# LPC_11C14.net
KiCad netlist of a schematic drawn in Altium Designer
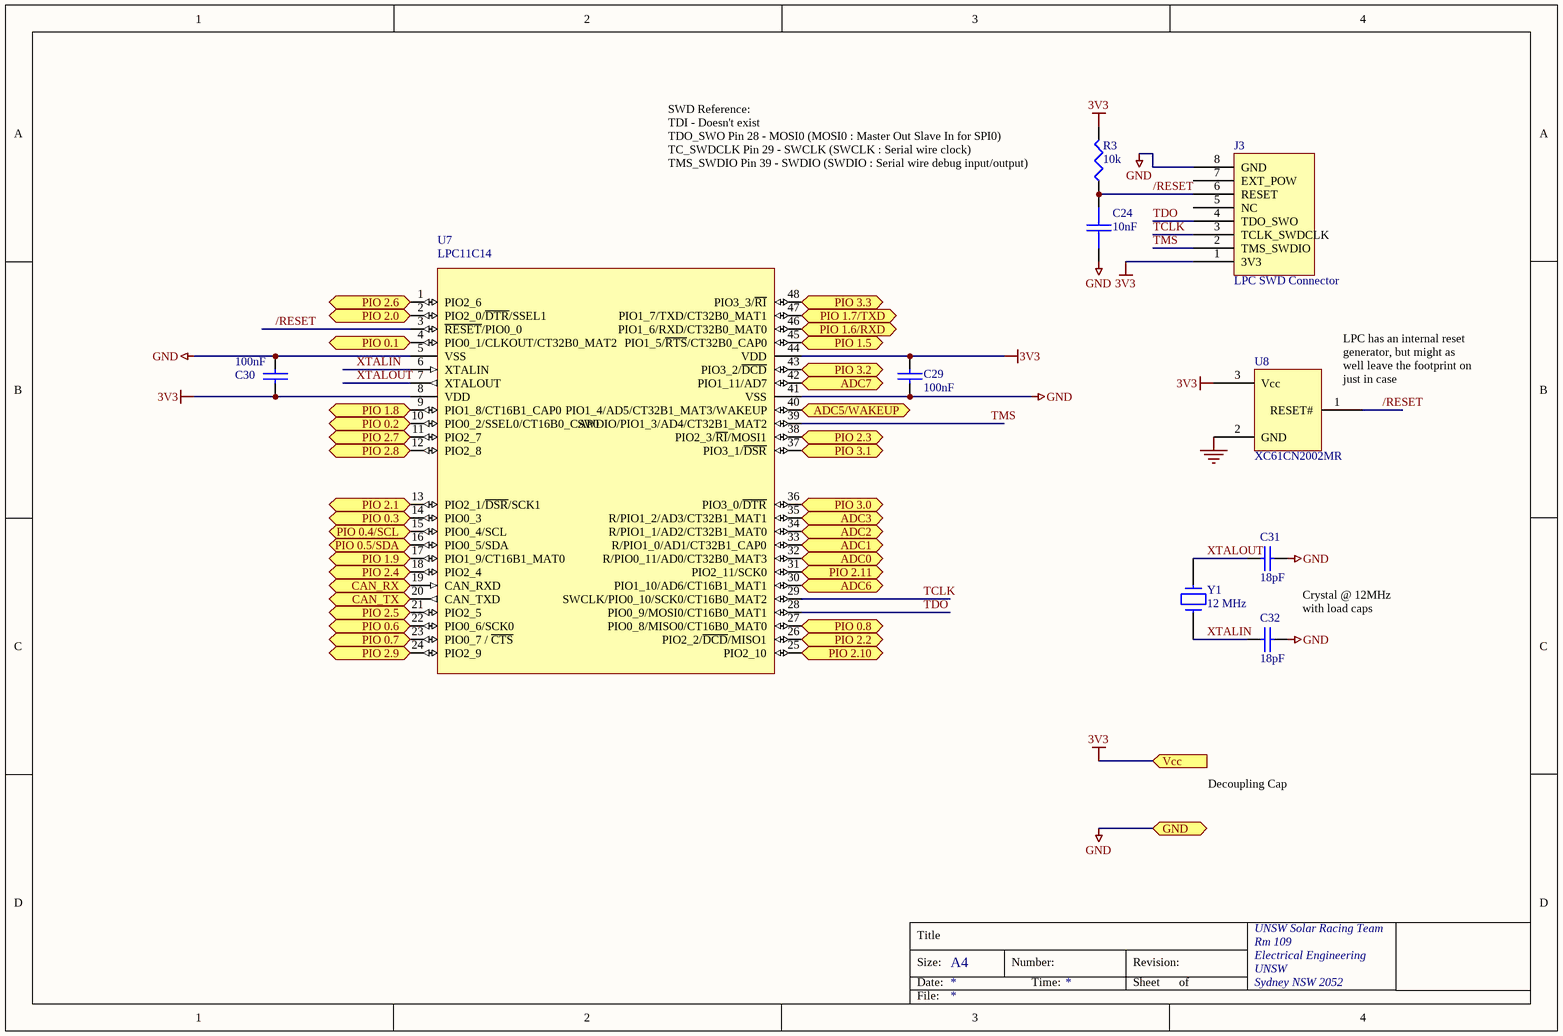
[diagram p0: LPC_11C14.SchDoc]

(export (version "E")
  (design (tool "Eeschema 10.0.6"))
  (components
    (comp (ref "C24")
      (value "10nF")
      (footprint "0603")
      (description "Capacitor")
      (libsource (lib "SunswiftLib20030312RR") (part "CAP"))
    )
    (comp (ref "C29")
      (value "100nF")
      (footprint "0603")
      (description "Capacitor")
      (libsource (lib "*") (part "CAP"))
    )
    (comp (ref "C30")
      (value "100nF")
      (footprint "0603")
      (description "Capacitor")
      (libsource (lib "*") (part "CAP"))
    )
    (comp (ref "C31")
      (value "18pF")
      (footprint "0603")
      (description "Capacitor")
      (libsource (lib "*") (part "CAP"))
    )
    (comp (ref "C32")
      (value "18pF")
      (footprint "0603")
      (description "Capacitor")
      (libsource (lib "*") (part "CAP"))
    )
    (comp (ref "J3")
      (value "LPC SWD Connector")
      (footprint "IDC8")
      (libsource (lib "2009_BatteryMaster") (part "LPCLink_Connector"))
    )
    (comp (ref "R3")
      (value "10k")
      (footprint "0603")
      (description "Resistor")
      (libsource (lib "SunswiftLib20030312RR") (part "RES1"))
    )
    (comp (ref "U7")
      (value "LPC11C14")
      (footprint "QFP48-long")
      (libsource (lib "LPC") (part "LPC11C14_Full"))
    )
    (comp (ref "U8")
      (value "XC61CN2002MR")
      (footprint "SOT23-3")
      (description "SOT23 reset generator")
      (libsource (lib "*") (part "XC61F"))
    )
    (comp (ref "Y1")
      (value "12 MHz")
      (footprint "HC49/4H")
      (description "Crystal")
      (libsource (lib "*") (part "CRYSTAL"))
    )
  )
  (nets
    (net (code "1") (name "/ADC0") (class "Default")
      (node (ref "U7") (pin "32") (pinfunction "R/PIO0_11/AD0/CT32B0_MAT3_32") (pintype "bidirectional"))
    )
    (net (code "2") (name "/ADC1") (class "Default")
      (node (ref "U7") (pin "33") (pinfunction "R/PIO1_0/AD1/CT32B1_CAP0_33") (pintype "bidirectional"))
    )
    (net (code "3") (name "/ADC2") (class "Default")
      (node (ref "U7") (pin "34") (pinfunction "R/PIO1_1/AD2/CT32B1_MAT0_34") (pintype "bidirectional"))
    )
    (net (code "4") (name "/ADC3") (class "Default")
      (node (ref "U7") (pin "35") (pinfunction "R/PIO1_2/AD3/CT32B1_MAT1_35") (pintype "bidirectional"))
    )
    (net (code "5") (name "/ADC5{slash}WAKEUP") (class "Default")
      (node (ref "U7") (pin "40") (pinfunction "PIO1_4/AD5/CT32B1_MAT3/WAKEUP_40") (pintype "bidirectional"))
    )
    (net (code "6") (name "/ADC6") (class "Default")
      (node (ref "U7") (pin "30") (pinfunction "PIO1_10/AD6/CT16B1_MAT1_30") (pintype "bidirectional"))
    )
    (net (code "7") (name "/ADC7") (class "Default")
      (node (ref "U7") (pin "42") (pinfunction "PIO1_11/AD7_42") (pintype "bidirectional"))
    )
    (net (code "8") (name "/CAN_RX") (class "Default")
      (node (ref "U7") (pin "19") (pinfunction "CAN_RXD_19") (pintype "input"))
    )
    (net (code "9") (name "/CAN_TX") (class "Default")
      (node (ref "U7") (pin "20") (pinfunction "CAN_TXD_20") (pintype "output"))
    )
    (net (code "10") (name "/PIO 0.1") (class "Default")
      (node (ref "U7") (pin "4") (pinfunction "PIO0_1/CLKOUT/CT32B0_MAT2_4") (pintype "bidirectional"))
    )
    (net (code "11") (name "/PIO 0.2") (class "Default")
      (node (ref "U7") (pin "10") (pinfunction "PIO0_2/SSEL0/CT16B0_CAP0_10") (pintype "bidirectional"))
    )
    (net (code "12") (name "/PIO 0.3") (class "Default")
      (node (ref "U7") (pin "14") (pinfunction "PIO0_3_14") (pintype "bidirectional"))
    )
    (net (code "13") (name "/PIO 0.4{slash}SCL") (class "Default")
      (node (ref "U7") (pin "15") (pinfunction "PIO0_4/SCL_15") (pintype "bidirectional"))
    )
    (net (code "14") (name "/PIO 0.5{slash}SDA") (class "Default")
      (node (ref "U7") (pin "16") (pinfunction "PIO0_5/SDA_16") (pintype "bidirectional"))
    )
    (net (code "15") (name "/PIO 0.6") (class "Default")
      (node (ref "U7") (pin "22") (pinfunction "PIO0_6/SCK0_22") (pintype "bidirectional"))
    )
    (net (code "16") (name "/PIO 0.7") (class "Default")
      (node (ref "U7") (pin "23") (pinfunction "PIO0_7_/_~{CTS}_23") (pintype "bidirectional"))
    )
    (net (code "17") (name "/PIO 0.8") (class "Default")
      (node (ref "U7") (pin "27") (pinfunction "PIO0_8/MISO0/CT16B0_MAT0_27") (pintype "bidirectional"))
    )
    (net (code "18") (name "/PIO 1.5") (class "Default")
      (node (ref "U7") (pin "45") (pinfunction "PIO1_5/~{RTS}/CT32B0_CAP0_45") (pintype "bidirectional"))
    )
    (net (code "19") (name "/PIO 1.6{slash}RXD") (class "Default")
      (node (ref "U7") (pin "46") (pinfunction "PIO1_6/RXD/CT32B0_MAT0_46") (pintype "bidirectional"))
    )
    (net (code "20") (name "/PIO 1.7{slash}TXD") (class "Default")
      (node (ref "U7") (pin "47") (pinfunction "PIO1_7/TXD/CT32B0_MAT1_47") (pintype "bidirectional"))
    )
    (net (code "21") (name "/PIO 1.8") (class "Default")
      (node (ref "U7") (pin "9") (pinfunction "PIO1_8/CT16B1_CAP0_9") (pintype "bidirectional"))
    )
    (net (code "22") (name "/PIO 1.9") (class "Default")
      (node (ref "U7") (pin "17") (pinfunction "PIO1_9/CT16B1_MAT0_17") (pintype "bidirectional"))
    )
    (net (code "23") (name "/PIO 2.0") (class "Default")
      (node (ref "U7") (pin "2") (pinfunction "PIO2_0/~{DTR}/SSEL1_2") (pintype "bidirectional"))
    )
    (net (code "24") (name "/PIO 2.1") (class "Default")
      (node (ref "U7") (pin "13") (pinfunction "PIO2_1/~{DSR}/SCK1_13") (pintype "bidirectional"))
    )
    (net (code "25") (name "/PIO 2.2") (class "Default")
      (node (ref "U7") (pin "26") (pinfunction "PIO2_2/~{DCD}/MISO1_26") (pintype "bidirectional"))
    )
    (net (code "26") (name "/PIO 2.3") (class "Default")
      (node (ref "U7") (pin "38") (pinfunction "PIO2_3/~{RI}/MOSI1_38") (pintype "bidirectional"))
    )
    (net (code "27") (name "/PIO 2.4") (class "Default")
      (node (ref "U7") (pin "18") (pinfunction "PIO2_4_18") (pintype "bidirectional"))
    )
    (net (code "28") (name "/PIO 2.5") (class "Default")
      (node (ref "U7") (pin "21") (pinfunction "PIO2_5_21") (pintype "bidirectional"))
    )
    (net (code "29") (name "/PIO 2.6") (class "Default")
      (node (ref "U7") (pin "1") (pinfunction "PIO2_6_1") (pintype "bidirectional"))
    )
    (net (code "30") (name "/PIO 2.7") (class "Default")
      (node (ref "U7") (pin "11") (pinfunction "PIO2_7_11") (pintype "bidirectional"))
    )
    (net (code "31") (name "/PIO 2.8") (class "Default")
      (node (ref "U7") (pin "12") (pinfunction "PIO2_8_12") (pintype "bidirectional"))
    )
    (net (code "32") (name "/PIO 2.9") (class "Default")
      (node (ref "U7") (pin "24") (pinfunction "PIO2_9_24") (pintype "bidirectional"))
    )
    (net (code "33") (name "/PIO 2.10") (class "Default")
      (node (ref "U7") (pin "25") (pinfunction "PIO2_10_25") (pintype "bidirectional"))
    )
    (net (code "34") (name "/PIO 2.11") (class "Default")
      (node (ref "U7") (pin "31") (pinfunction "PIO2_11/SCK0_31") (pintype "bidirectional"))
    )
    (net (code "35") (name "/PIO 3.0") (class "Default")
      (node (ref "U7") (pin "36") (pinfunction "PIO3_0/~{DTR}_36") (pintype "bidirectional"))
    )
    (net (code "36") (name "/PIO 3.1") (class "Default")
      (node (ref "U7") (pin "37") (pinfunction "PIO3_1/~{DSR}_37") (pintype "bidirectional"))
    )
    (net (code "37") (name "/PIO 3.2") (class "Default")
      (node (ref "U7") (pin "43") (pinfunction "PIO3_2/~{DCD}_43") (pintype "bidirectional"))
    )
    (net (code "38") (name "/PIO 3.3") (class "Default")
      (node (ref "U7") (pin "48") (pinfunction "PIO3_3/~{RI}_48") (pintype "bidirectional"))
    )
    (net (code "39") (name "/TCLK") (class "Default")
      (node (ref "J3") (pin "3") (pinfunction "TCLK_SWDCLK_3") (pintype "passive"))
      (node (ref "U7") (pin "29") (pinfunction "SWCLK/PIO0_10/SCK0/CT16B0_MAT2_29") (pintype "bidirectional"))
    )
    (net (code "40") (name "/TDO") (class "Default")
      (node (ref "J3") (pin "4") (pinfunction "TDO_SWO_4") (pintype "passive"))
      (node (ref "U7") (pin "28") (pinfunction "PIO0_9/MOSI0/CT16B0_MAT1_28") (pintype "bidirectional"))
    )
    (net (code "41") (name "/TMS") (class "Default")
      (node (ref "J3") (pin "2") (pinfunction "TMS_SWDIO_2") (pintype "passive"))
      (node (ref "U7") (pin "39") (pinfunction "SWDIO/PIO1_3/AD4/CT32B1_MAT2_39") (pintype "bidirectional"))
    )
    (net (code "42") (name "/XTALIN") (class "Default")
      (node (ref "C32") (pin "1") (pinfunction "1_1") (pintype "passive"))
      (node (ref "U7") (pin "6") (pinfunction "XTALIN_6") (pintype "input"))
      (node (ref "Y1") (pin "1") (pinfunction "1_1") (pintype "passive"))
    )
    (net (code "43") (name "/XTALOUT") (class "Default")
      (node (ref "C31") (pin "1") (pinfunction "1_1") (pintype "passive"))
      (node (ref "U7") (pin "7") (pinfunction "XTALOUT_7") (pintype "output"))
      (node (ref "Y1") (pin "2") (pinfunction "2_2") (pintype "passive"))
    )
    (net (code "44") (name "/{slash}RESET") (class "Default")
      (node (ref "C24") (pin "1") (pinfunction "1_1") (pintype "passive"))
      (node (ref "J3") (pin "6") (pinfunction "RESET_6") (pintype "passive"))
      (node (ref "R3") (pin "1") (pinfunction "1_1") (pintype "passive"))
      (node (ref "U7") (pin "3") (pinfunction "~{RESET}/PIO0_0_3") (pintype "bidirectional"))
      (node (ref "U8") (pin "1") (pinfunction "RESET#_1") (pintype "passive"))
    )
    (net (code "45") (name "3V3") (class "Default")
      (node (ref "C29") (pin "1") (pinfunction "1_1") (pintype "passive"))
      (node (ref "C30") (pin "2") (pinfunction "2_2") (pintype "passive"))
      (node (ref "J3") (pin "1") (pinfunction "3V3_1") (pintype "passive"))
      (node (ref "R3") (pin "2") (pinfunction "2_2") (pintype "passive"))
      (node (ref "U7") (pin "44") (pinfunction "VDD_44") (pintype "power_in"))
      (node (ref "U7") (pin "8") (pinfunction "VDD_8") (pintype "power_in"))
      (node (ref "U8") (pin "3") (pinfunction "Vcc_3") (pintype "passive"))
    )
    (net (code "46") (name "GND") (class "Default")
      (node (ref "C24") (pin "2") (pinfunction "2_2") (pintype "passive"))
      (node (ref "C29") (pin "2") (pinfunction "2_2") (pintype "passive"))
      (node (ref "C30") (pin "1") (pinfunction "1_1") (pintype "passive"))
      (node (ref "C31") (pin "2") (pinfunction "2_2") (pintype "passive"))
      (node (ref "C32") (pin "2") (pinfunction "2_2") (pintype "passive"))
      (node (ref "J3") (pin "8") (pinfunction "GND_8") (pintype "passive"))
      (node (ref "U7") (pin "41") (pinfunction "VSS_41") (pintype "power_in"))
      (node (ref "U7") (pin "5") (pinfunction "VSS_5") (pintype "power_in"))
      (node (ref "U8") (pin "2") (pinfunction "GND_2") (pintype "passive"))
    )
    (net (code "47") (name "unconnected-(J3-EXT_POW-Pad7)") (class "Default")
      (node (ref "J3") (pin "7") (pinfunction "EXT_POW_7") (pintype "passive"))
    )
    (net (code "48") (name "unconnected-(J3-NC-Pad5)") (class "Default")
      (node (ref "J3") (pin "5") (pinfunction "NC_5") (pintype "passive"))
    )
  )
)
